# connector.net
KiCad netlist of a schematic drawn in Altium Designer
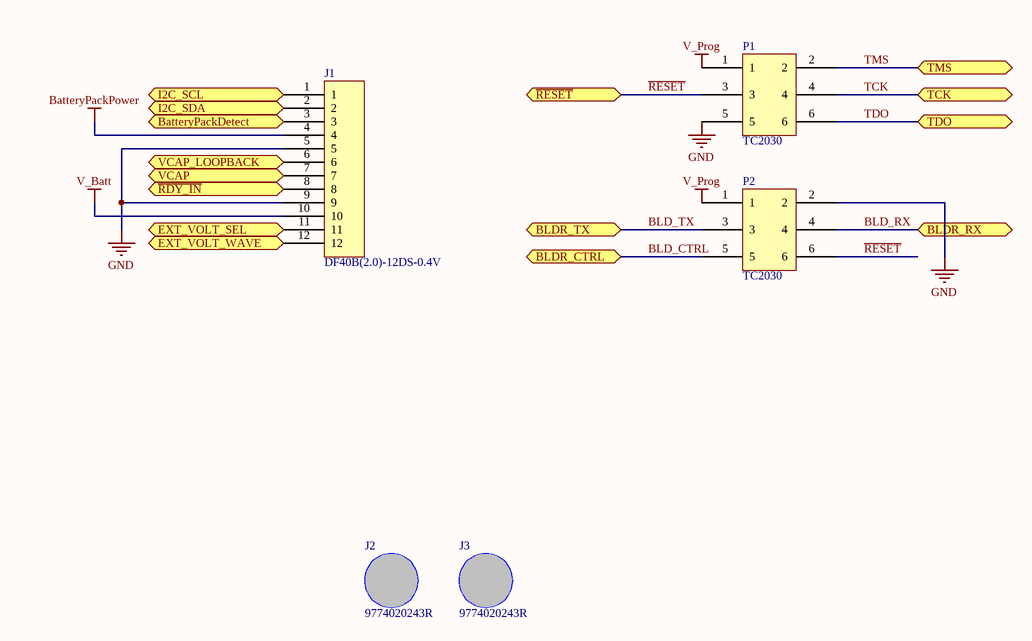
[diagram p0: connector.SchDoc]

(export (version "E")
  (design (tool "Eeschema 10.0.6"))
  (components
    (comp (ref "J1")
      (value "DF40B(2.0)-12DS-0.4V")
      (footprint "DF40B(2.0)-12DS-0.4V")
      (description "Hirose BM20 Series, 0.4mm pitch, 2mm stack height, 12 pos, header")
      (libsource (lib "connectors") (part "DF40B(2.0)-12DS-0.4V"))
    )
    (comp (ref "J2")
      (value "9774020243R")
      (footprint "9774020243R")
      (description "2 mm stack height, m2 standoff")
      (libsource (lib "connectors") (part "9774020243R"))
    )
    (comp (ref "J3")
      (value "9774020243R")
      (footprint "9774020243R")
      (description "2 mm stack height, m2 standoff")
      (libsource (lib "connectors") (part "9774020243R"))
    )
    (comp (ref "P1")
      (value "TC2030")
      (footprint "TC2030-IDC-NLFP")
      (description "TC2030-MCP-NL")
      (libsource (lib "connectors") (part "TC2030"))
    )
    (comp (ref "P2")
      (value "TC2030")
      (footprint "TC2030-IDC-NLFP")
      (description "TC2030-MCP-NL")
      (libsource (lib "connectors") (part "TC2030"))
    )
  )
  (nets
    (net (code "1") (name "/BLD_CTRL") (class "Default")
      (node (ref "P2") (pin "5") (pinfunction "5_5") (pintype "passive"))
    )
    (net (code "2") (name "/BLD_RX") (class "Default")
      (node (ref "P2") (pin "4") (pinfunction "4_4") (pintype "passive"))
    )
    (net (code "3") (name "/BLD_TX") (class "Default")
      (node (ref "P2") (pin "3") (pinfunction "3_3") (pintype "passive"))
    )
    (net (code "4") (name "/BatteryPackDetect") (class "Default")
      (node (ref "J1") (pin "3") (pinfunction "3_3") (pintype "passive"))
    )
    (net (code "5") (name "/EXT_VOLT_SEL") (class "Default")
      (node (ref "J1") (pin "11") (pinfunction "11_11") (pintype "passive"))
    )
    (net (code "6") (name "/EXT_VOLT_WAVE") (class "Default")
      (node (ref "J1") (pin "12") (pinfunction "12_12") (pintype "passive"))
    )
    (net (code "7") (name "/I2C_SCL") (class "Default")
      (node (ref "J1") (pin "1") (pinfunction "1_1") (pintype "passive"))
    )
    (net (code "8") (name "/I2C_SDA") (class "Default")
      (node (ref "J1") (pin "2") (pinfunction "2_2") (pintype "passive"))
    )
    (net (code "9") (name "/TCK") (class "Default")
      (node (ref "P1") (pin "4") (pinfunction "4_4") (pintype "passive"))
    )
    (net (code "10") (name "/TDO") (class "Default")
      (node (ref "P1") (pin "6") (pinfunction "6_6") (pintype "passive"))
    )
    (net (code "11") (name "/TMS") (class "Default")
      (node (ref "P1") (pin "2") (pinfunction "2_2") (pintype "passive"))
    )
    (net (code "12") (name "/VCAP") (class "Default")
      (node (ref "J1") (pin "7") (pinfunction "7_7") (pintype "passive"))
    )
    (net (code "13") (name "/VCAP_LOOPBACK") (class "Default")
      (node (ref "J1") (pin "6") (pinfunction "6_6") (pintype "passive"))
    )
    (net (code "14") (name "/~{RDY_IN}") (class "Default")
      (node (ref "J1") (pin "8") (pinfunction "8_8") (pintype "passive"))
    )
    (net (code "15") (name "/~{RESET}") (class "Default")
      (node (ref "P1") (pin "3") (pinfunction "3_3") (pintype "passive"))
      (node (ref "P2") (pin "6") (pinfunction "6_6") (pintype "passive"))
    )
    (net (code "16") (name "BatteryPackPower") (class "Default")
      (node (ref "J1") (pin "4") (pinfunction "4_4") (pintype "passive"))
    )
    (net (code "17") (name "GND") (class "Default")
      (node (ref "J1") (pin "5") (pinfunction "5_5") (pintype "passive"))
      (node (ref "J1") (pin "9") (pinfunction "9_9") (pintype "passive"))
      (node (ref "P1") (pin "5") (pinfunction "5_5") (pintype "passive"))
      (node (ref "P2") (pin "2") (pinfunction "2_2") (pintype "passive"))
    )
    (net (code "18") (name "V_Batt") (class "Default")
      (node (ref "J1") (pin "10") (pinfunction "10_10") (pintype "passive"))
    )
    (net (code "19") (name "V_Prog") (class "Default")
      (node (ref "P1") (pin "1") (pinfunction "1_1") (pintype "passive"))
      (node (ref "P2") (pin "1") (pinfunction "1_1") (pintype "passive"))
    )
  )
)
